# Z-Control-V2.net
KiCad netlist of a schematic drawn in EAGLE
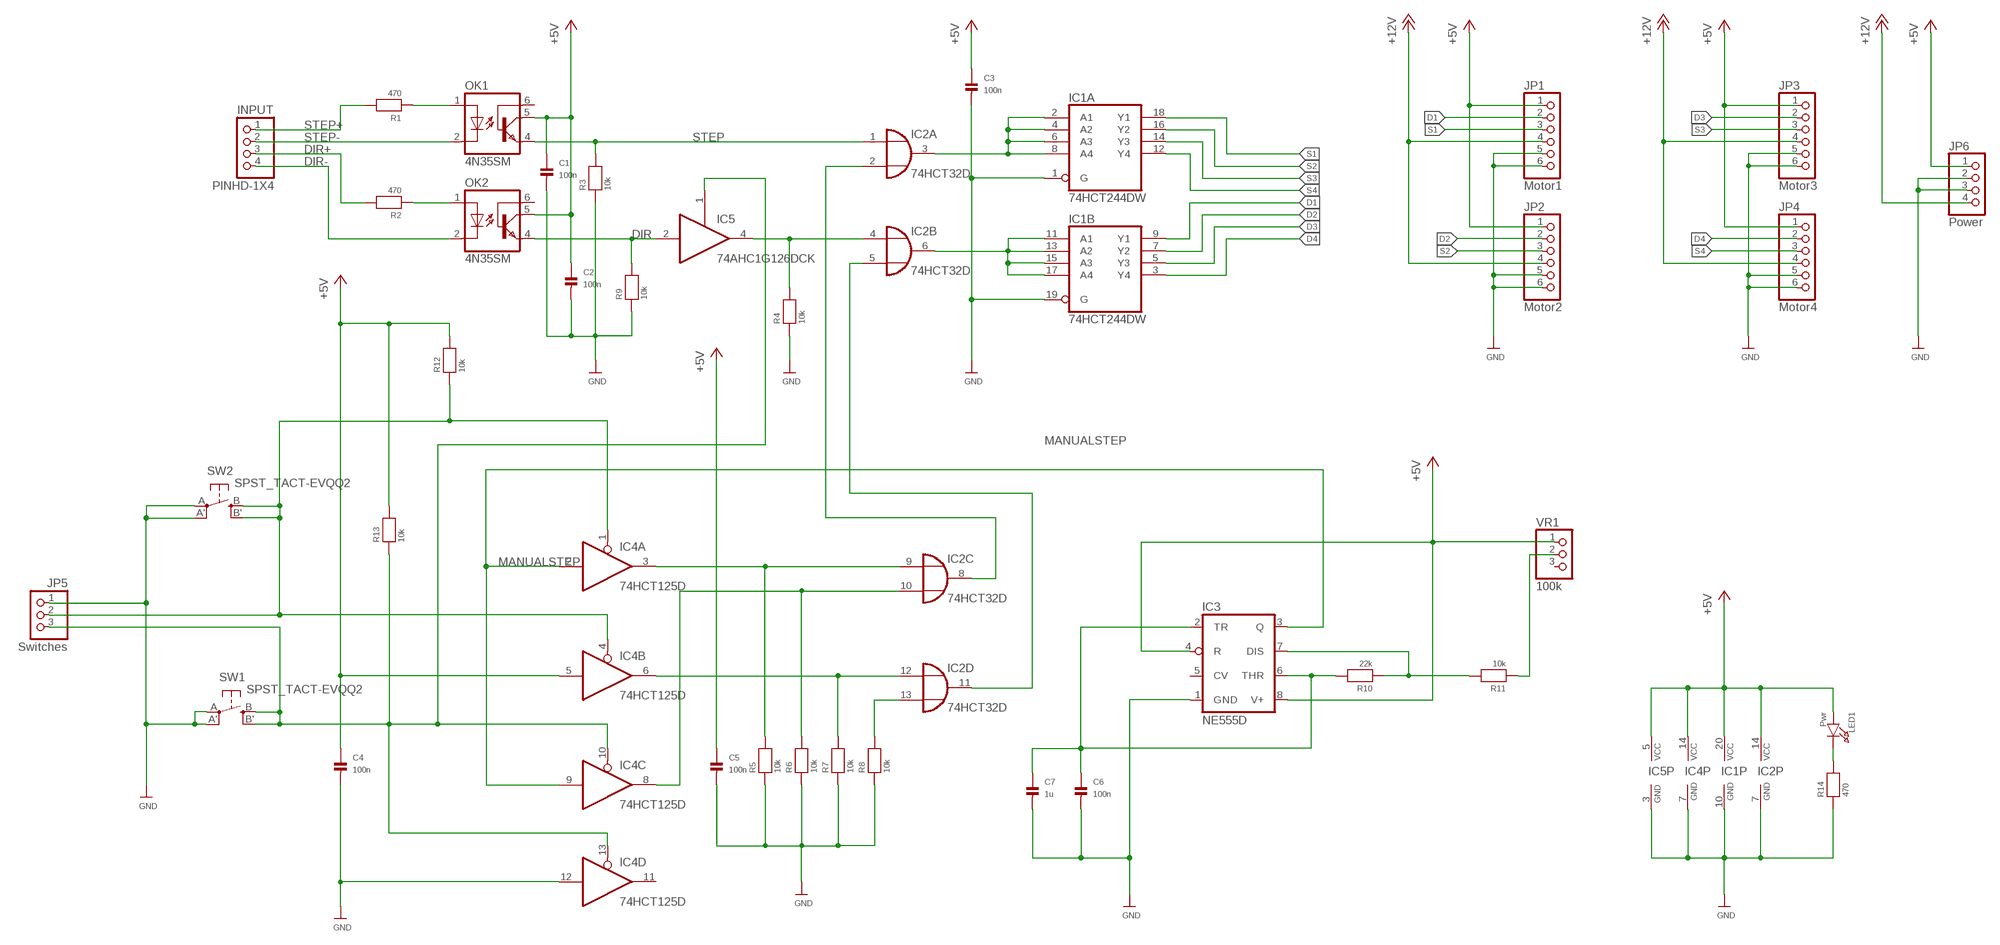
[diagram p0: schematic, sheet 1]

(export (version "E")
  (design (tool "Eeschema 10.0.6"))
  (components
    (comp (ref "C1")
      (value "100n")
      (footprint "eagle-import:_0805")
      (libsource (lib "eagle-import") (part "CAP_CERAMIC_0805"))
    )
    (comp (ref "C2")
      (value "100n")
      (footprint "eagle-import:_0805")
      (libsource (lib "eagle-import") (part "CAP_CERAMIC_0805"))
    )
    (comp (ref "C3")
      (value "100n")
      (footprint "eagle-import:_0805")
      (libsource (lib "eagle-import") (part "CAP_CERAMIC_0805"))
    )
    (comp (ref "C4")
      (value "100n")
      (footprint "eagle-import:_0805")
      (libsource (lib "eagle-import") (part "CAP_CERAMIC_0805"))
    )
    (comp (ref "C5")
      (value "100n")
      (footprint "eagle-import:_0805")
      (libsource (lib "eagle-import") (part "CAP_CERAMIC_0805"))
    )
    (comp (ref "C6")
      (value "100n")
      (footprint "eagle-import:_0805")
      (libsource (lib "eagle-import") (part "CAP_CERAMIC_0805"))
    )
    (comp (ref "C7")
      (value "1u")
      (footprint "eagle-import:_0805")
      (libsource (lib "eagle-import") (part "CAP_CERAMIC_0805"))
    )
    (comp (ref "IC1")
      (value "74HCT244DW")
      (footprint "eagle-import:SO20W")
      (libsource (lib "eagle-import") (part "74244DWHCT"))
    )
    (comp (ref "IC2")
      (value "74HCT32D")
      (footprint "eagle-import:SO14")
      (libsource (lib "eagle-import") (part "7432DHCT"))
    )
    (comp (ref "IC3")
      (value "NE555D")
      (footprint "eagle-import:SO08")
      (libsource (lib "eagle-import") (part "555DNE"))
    )
    (comp (ref "IC4")
      (value "74HCT125D")
      (footprint "eagle-import:SO14")
      (libsource (lib "eagle-import") (part "74125DHCT"))
    )
    (comp (ref "IC5")
      (value "74AHC1G126DCK")
      (footprint "eagle-import:SC70-5")
      (libsource (lib "eagle-import") (part "741G126DCKAHC"))
    )
    (comp (ref "INPUT")
      (value "PINHD-1X4")
      (footprint "eagle-import:1X04-BIG")
      (libsource (lib "eagle-import") (part "PINHD-1X4"))
    )
    (comp (ref "JP1")
      (value "Motor1")
      (footprint "eagle-import:1X06")
      (libsource (lib "eagle-import") (part "PINHD-1X6"))
    )
    (comp (ref "JP2")
      (value "Motor2")
      (footprint "eagle-import:1X06")
      (libsource (lib "eagle-import") (part "PINHD-1X6"))
    )
    (comp (ref "JP3")
      (value "Motor3")
      (footprint "eagle-import:1X06")
      (libsource (lib "eagle-import") (part "PINHD-1X6"))
    )
    (comp (ref "JP4")
      (value "Motor4")
      (footprint "eagle-import:1X06")
      (libsource (lib "eagle-import") (part "PINHD-1X6"))
    )
    (comp (ref "JP5")
      (value "Switches")
      (footprint "eagle-import:1X03")
      (libsource (lib "eagle-import") (part "PINHD-1X3"))
    )
    (comp (ref "JP6")
      (value "Power")
      (footprint "eagle-import:1X04-BIG")
      (libsource (lib "eagle-import") (part "PINHD-1X4"))
    )
    (comp (ref "LED1")
      (value "Pwr")
      (footprint "eagle-import:CHIPLED_0805")
      (libsource (lib "eagle-import") (part "LED0805"))
    )
    (comp (ref "OK1")
      (value "4N35SM")
      (footprint "eagle-import:DIL6-SMD")
      (fields (field (name "MF") "FAIRCHILD SEMICONDUCTOR") (field (name "MPN") "4N35S-M"))
      (libsource (lib "eagle-import") (part "4N?MS35"))
    )
    (comp (ref "OK2")
      (value "4N35SM")
      (footprint "eagle-import:DIL6-SMD")
      (fields (field (name "MF") "FAIRCHILD SEMICONDUCTOR") (field (name "MPN") "4N35S-M"))
      (libsource (lib "eagle-import") (part "4N?MS35"))
    )
    (comp (ref "R1")
      (value "470")
      (footprint "eagle-import:_0805")
      (libsource (lib "eagle-import") (part "RESISTOR_0805"))
    )
    (comp (ref "R2")
      (value "470")
      (footprint "eagle-import:_0805")
      (libsource (lib "eagle-import") (part "RESISTOR_0805"))
    )
    (comp (ref "R3")
      (value "10k")
      (footprint "eagle-import:_0805")
      (libsource (lib "eagle-import") (part "RESISTOR_0805"))
    )
    (comp (ref "R4")
      (value "10k")
      (footprint "eagle-import:_0805")
      (libsource (lib "eagle-import") (part "RESISTOR_0805"))
    )
    (comp (ref "R5")
      (value "10k")
      (footprint "eagle-import:_0805")
      (libsource (lib "eagle-import") (part "RESISTOR_0805"))
    )
    (comp (ref "R6")
      (value "10k")
      (footprint "eagle-import:_0805")
      (libsource (lib "eagle-import") (part "RESISTOR_0805"))
    )
    (comp (ref "R7")
      (value "10k")
      (footprint "eagle-import:_0805")
      (libsource (lib "eagle-import") (part "RESISTOR_0805"))
    )
    (comp (ref "R8")
      (value "10k")
      (footprint "eagle-import:_0805")
      (libsource (lib "eagle-import") (part "RESISTOR_0805"))
    )
    (comp (ref "R9")
      (value "10k")
      (footprint "eagle-import:_0805")
      (libsource (lib "eagle-import") (part "RESISTOR_0805"))
    )
    (comp (ref "R10")
      (value "22k")
      (footprint "eagle-import:_0805")
      (libsource (lib "eagle-import") (part "RESISTOR_0805"))
    )
    (comp (ref "R11")
      (value "10k")
      (footprint "eagle-import:_0805")
      (libsource (lib "eagle-import") (part "RESISTOR_0805"))
    )
    (comp (ref "R12")
      (value "10k")
      (footprint "eagle-import:_0805")
      (libsource (lib "eagle-import") (part "RESISTOR_0805"))
    )
    (comp (ref "R13")
      (value "10k")
      (footprint "eagle-import:_0805")
      (libsource (lib "eagle-import") (part "RESISTOR_0805"))
    )
    (comp (ref "R14")
      (value "470")
      (footprint "eagle-import:_0805")
      (libsource (lib "eagle-import") (part "RESISTOR_0805"))
    )
    (comp (ref "SW1")
      (value "SPST_TACT-EVQQ2")
      (footprint "eagle-import:EVQ-Q2")
      (libsource (lib "eagle-import") (part "SPST_TACT-EVQQ2"))
    )
    (comp (ref "SW2")
      (value "SPST_TACT-EVQQ2")
      (footprint "eagle-import:EVQ-Q2")
      (libsource (lib "eagle-import") (part "SPST_TACT-EVQQ2"))
    )
    (comp (ref "VR1")
      (value "100k")
      (footprint "eagle-import:1X03_OVAL")
      (libsource (lib "eagle-import") (part "HEADER-1X3"))
    )
  )
  (nets
    (net (code "1") (name "+5V") (class "Default")
      (node (ref "C1") (pin "1") (pinfunction "P$1_1") (pintype "passive"))
      (node (ref "C2") (pin "1") (pinfunction "P$1_1") (pintype "passive"))
      (node (ref "C3") (pin "1") (pinfunction "P$1_1") (pintype "passive"))
      (node (ref "C4") (pin "1") (pinfunction "P$1_1") (pintype "passive"))
      (node (ref "C5") (pin "1") (pinfunction "P$1_1") (pintype "passive"))
      (node (ref "IC1") (pin "20") (pinfunction "VCC_20") (pintype "power_in"))
      (node (ref "IC2") (pin "14") (pinfunction "VCC_14") (pintype "power_in"))
      (node (ref "IC3") (pin "4") (pinfunction "R_4") (pintype "input"))
      (node (ref "IC3") (pin "8") (pinfunction "V+_8") (pintype "power_in"))
      (node (ref "IC4") (pin "14") (pinfunction "VCC_14") (pintype "power_in"))
      (node (ref "IC4") (pin "5") (pinfunction "I_5") (pintype "input"))
      (node (ref "IC5") (pin "5") (pinfunction "VCC_5") (pintype "power_in"))
      (node (ref "JP1") (pin "1") (pinfunction "1_1") (pintype "passive"))
      (node (ref "JP2") (pin "1") (pinfunction "1_1") (pintype "passive"))
      (node (ref "JP3") (pin "1") (pinfunction "1_1") (pintype "passive"))
      (node (ref "JP4") (pin "1") (pinfunction "1_1") (pintype "passive"))
      (node (ref "JP6") (pin "1") (pinfunction "1_1") (pintype "passive"))
      (node (ref "LED1") (pin "A") (pinfunction "A_A") (pintype "passive"))
      (node (ref "OK1") (pin "5") (pinfunction "COL_5") (pintype "passive"))
      (node (ref "OK2") (pin "5") (pinfunction "COL_5") (pintype "passive"))
      (node (ref "R12") (pin "2") (pinfunction "2_2") (pintype "passive"))
      (node (ref "R13") (pin "2") (pinfunction "2_2") (pintype "passive"))
      (node (ref "VR1") (pin "1") (pinfunction "1_1") (pintype "passive"))
    )
    (net (code "2") (name "+12V") (class "Default")
      (node (ref "JP1") (pin "4") (pinfunction "4_4") (pintype "passive"))
      (node (ref "JP2") (pin "4") (pinfunction "4_4") (pintype "passive"))
      (node (ref "JP3") (pin "4") (pinfunction "4_4") (pintype "passive"))
      (node (ref "JP4") (pin "4") (pinfunction "4_4") (pintype "passive"))
      (node (ref "JP6") (pin "4") (pinfunction "4_4") (pintype "passive"))
    )
    (net (code "3") (name "/DIR") (class "Default")
      (node (ref "IC5") (pin "2") (pinfunction "I_2") (pintype "input"))
      (node (ref "OK2") (pin "4") (pinfunction "EMI_4") (pintype "passive"))
      (node (ref "R9") (pin "2") (pinfunction "2_2") (pintype "passive"))
    )
    (net (code "4") (name "/DIR+") (class "Default")
      (node (ref "INPUT") (pin "3") (pinfunction "3_3") (pintype "passive"))
      (node (ref "R2") (pin "2") (pinfunction "2_2") (pintype "passive"))
    )
    (net (code "5") (name "/DIR-") (class "Default")
      (node (ref "INPUT") (pin "4") (pinfunction "4_4") (pintype "passive"))
      (node (ref "OK2") (pin "2") (pinfunction "C_2") (pintype "passive"))
    )
    (net (code "6") (name "/MANUALSTEP") (class "Default")
      (node (ref "IC3") (pin "3") (pinfunction "Q_3") (pintype "output"))
      (node (ref "IC4") (pin "2") (pinfunction "I_2") (pintype "input"))
      (node (ref "IC4") (pin "9") (pinfunction "I_9") (pintype "input"))
    )
    (net (code "7") (name "/STEP") (class "Default")
      (node (ref "IC2") (pin "1") (pinfunction "I0_1") (pintype "input"))
      (node (ref "OK1") (pin "4") (pinfunction "EMI_4") (pintype "passive"))
      (node (ref "R3") (pin "2") (pinfunction "2_2") (pintype "passive"))
    )
    (net (code "8") (name "/STEP+") (class "Default")
      (node (ref "INPUT") (pin "1") (pinfunction "1_1") (pintype "passive"))
      (node (ref "R1") (pin "2") (pinfunction "2_2") (pintype "passive"))
    )
    (net (code "9") (name "/STEP-") (class "Default")
      (node (ref "INPUT") (pin "2") (pinfunction "2_2") (pintype "passive"))
      (node (ref "OK1") (pin "2") (pinfunction "C_2") (pintype "passive"))
    )
    (net (code "10") (name "D1") (class "Default")
      (node (ref "IC1") (pin "9") (pinfunction "Y1_9") (pintype "tri_state"))
      (node (ref "JP1") (pin "2") (pinfunction "2_2") (pintype "passive"))
    )
    (net (code "11") (name "D2") (class "Default")
      (node (ref "IC1") (pin "7") (pinfunction "Y2_7") (pintype "tri_state"))
      (node (ref "JP2") (pin "2") (pinfunction "2_2") (pintype "passive"))
    )
    (net (code "12") (name "D3") (class "Default")
      (node (ref "IC1") (pin "5") (pinfunction "Y3_5") (pintype "tri_state"))
      (node (ref "JP3") (pin "2") (pinfunction "2_2") (pintype "passive"))
    )
    (net (code "13") (name "D4") (class "Default")
      (node (ref "IC1") (pin "3") (pinfunction "Y4_3") (pintype "tri_state"))
      (node (ref "JP4") (pin "2") (pinfunction "2_2") (pintype "passive"))
    )
    (net (code "14") (name "GND") (class "Default")
      (node (ref "C1") (pin "2") (pinfunction "P$2_2") (pintype "passive"))
      (node (ref "C2") (pin "2") (pinfunction "P$2_2") (pintype "passive"))
      (node (ref "C3") (pin "2") (pinfunction "P$2_2") (pintype "passive"))
      (node (ref "C4") (pin "2") (pinfunction "P$2_2") (pintype "passive"))
      (node (ref "C5") (pin "2") (pinfunction "P$2_2") (pintype "passive"))
      (node (ref "C6") (pin "2") (pinfunction "P$2_2") (pintype "passive"))
      (node (ref "C7") (pin "2") (pinfunction "P$2_2") (pintype "passive"))
      (node (ref "IC1") (pin "1") (pinfunction "G_1") (pintype "input"))
      (node (ref "IC1") (pin "10") (pinfunction "GND_10") (pintype "power_in"))
      (node (ref "IC1") (pin "19") (pinfunction "G_19") (pintype "input"))
      (node (ref "IC2") (pin "7") (pinfunction "GND_7") (pintype "power_in"))
      (node (ref "IC3") (pin "1") (pinfunction "GND_1") (pintype "power_in"))
      (node (ref "IC4") (pin "12") (pinfunction "I_12") (pintype "input"))
      (node (ref "IC4") (pin "7") (pinfunction "GND_7") (pintype "power_in"))
      (node (ref "IC5") (pin "3") (pinfunction "GND_3") (pintype "power_in"))
      (node (ref "JP1") (pin "5") (pinfunction "5_5") (pintype "passive"))
      (node (ref "JP1") (pin "6") (pinfunction "6_6") (pintype "passive"))
      (node (ref "JP2") (pin "5") (pinfunction "5_5") (pintype "passive"))
      (node (ref "JP2") (pin "6") (pinfunction "6_6") (pintype "passive"))
      (node (ref "JP3") (pin "5") (pinfunction "5_5") (pintype "passive"))
      (node (ref "JP3") (pin "6") (pinfunction "6_6") (pintype "passive"))
      (node (ref "JP4") (pin "5") (pinfunction "5_5") (pintype "passive"))
      (node (ref "JP4") (pin "6") (pinfunction "6_6") (pintype "passive"))
      (node (ref "JP5") (pin "1") (pinfunction "1_1") (pintype "passive"))
      (node (ref "JP6") (pin "2") (pinfunction "2_2") (pintype "passive"))
      (node (ref "JP6") (pin "3") (pinfunction "3_3") (pintype "passive"))
      (node (ref "R14") (pin "1") (pinfunction "1_1") (pintype "passive"))
      (node (ref "R3") (pin "1") (pinfunction "1_1") (pintype "passive"))
      (node (ref "R4") (pin "1") (pinfunction "1_1") (pintype "passive"))
      (node (ref "R5") (pin "1") (pinfunction "1_1") (pintype "passive"))
      (node (ref "R6") (pin "1") (pinfunction "1_1") (pintype "passive"))
      (node (ref "R7") (pin "1") (pinfunction "1_1") (pintype "passive"))
      (node (ref "R8") (pin "1") (pinfunction "1_1") (pintype "passive"))
      (node (ref "R9") (pin "1") (pinfunction "1_1") (pintype "passive"))
      (node (ref "SW1") (pin "A") (pinfunction "P_A") (pintype "passive"))
      (node (ref "SW1") (pin "A'") (pinfunction "P1_A'") (pintype "passive"))
      (node (ref "SW2") (pin "A") (pinfunction "P_A") (pintype "passive"))
      (node (ref "SW2") (pin "A'") (pinfunction "P1_A'") (pintype "passive"))
    )
    (net (code "15") (name "Net-(C6-P$1)") (class "Default")
      (node (ref "C6") (pin "1") (pinfunction "P$1_1") (pintype "passive"))
      (node (ref "C7") (pin "1") (pinfunction "P$1_1") (pintype "passive"))
      (node (ref "IC3") (pin "2") (pinfunction "TR_2") (pintype "input"))
      (node (ref "IC3") (pin "6") (pinfunction "THR_6") (pintype "input"))
      (node (ref "R10") (pin "2") (pinfunction "2_2") (pintype "passive"))
    )
    (net (code "16") (name "Net-(IC1A-A1)") (class "Default")
      (node (ref "IC1") (pin "2") (pinfunction "A1_2") (pintype "input"))
      (node (ref "IC1") (pin "4") (pinfunction "A2_4") (pintype "input"))
      (node (ref "IC1") (pin "6") (pinfunction "A3_6") (pintype "input"))
      (node (ref "IC1") (pin "8") (pinfunction "A4_8") (pintype "input"))
      (node (ref "IC2") (pin "3") (pinfunction "O_3") (pintype "output"))
    )
    (net (code "17") (name "Net-(IC1B-A1)") (class "Default")
      (node (ref "IC1") (pin "11") (pinfunction "A1_11") (pintype "input"))
      (node (ref "IC1") (pin "13") (pinfunction "A2_13") (pintype "input"))
      (node (ref "IC1") (pin "15") (pinfunction "A3_15") (pintype "input"))
      (node (ref "IC1") (pin "17") (pinfunction "A4_17") (pintype "input"))
      (node (ref "IC2") (pin "6") (pinfunction "O_6") (pintype "output"))
    )
    (net (code "18") (name "Net-(IC2A-I1)") (class "Default")
      (node (ref "IC2") (pin "2") (pinfunction "I1_2") (pintype "input"))
      (node (ref "IC2") (pin "8") (pinfunction "O_8") (pintype "output"))
    )
    (net (code "19") (name "Net-(IC2B-I0)") (class "Default")
      (node (ref "IC2") (pin "4") (pinfunction "I0_4") (pintype "input"))
      (node (ref "IC5") (pin "4") (pinfunction "O_4") (pintype "output"))
      (node (ref "R4") (pin "2") (pinfunction "2_2") (pintype "passive"))
    )
    (net (code "20") (name "Net-(IC2B-I1)") (class "Default")
      (node (ref "IC2") (pin "11") (pinfunction "O_11") (pintype "output"))
      (node (ref "IC2") (pin "5") (pinfunction "I1_5") (pintype "input"))
    )
    (net (code "21") (name "Net-(IC2C-I0)") (class "Default")
      (node (ref "IC2") (pin "9") (pinfunction "I0_9") (pintype "input"))
      (node (ref "IC4") (pin "3") (pinfunction "O_3") (pintype "tri_state"))
      (node (ref "R5") (pin "2") (pinfunction "2_2") (pintype "passive"))
    )
    (net (code "22") (name "Net-(IC2C-I1)") (class "Default")
      (node (ref "IC2") (pin "10") (pinfunction "I1_10") (pintype "input"))
      (node (ref "IC4") (pin "8") (pinfunction "O_8") (pintype "tri_state"))
      (node (ref "R6") (pin "2") (pinfunction "2_2") (pintype "passive"))
    )
    (net (code "23") (name "Net-(IC2D-I0)") (class "Default")
      (node (ref "IC2") (pin "12") (pinfunction "I0_12") (pintype "input"))
      (node (ref "IC4") (pin "6") (pinfunction "O_6") (pintype "tri_state"))
      (node (ref "R7") (pin "2") (pinfunction "2_2") (pintype "passive"))
    )
    (net (code "24") (name "Net-(IC2D-I1)") (class "Default")
      (node (ref "IC2") (pin "13") (pinfunction "I1_13") (pintype "input"))
      (node (ref "R8") (pin "2") (pinfunction "2_2") (pintype "passive"))
    )
    (net (code "25") (name "Net-(IC3-DIS)") (class "Default")
      (node (ref "IC3") (pin "7") (pinfunction "DIS_7") (pintype "input"))
      (node (ref "R10") (pin "1") (pinfunction "1_1") (pintype "passive"))
      (node (ref "R11") (pin "2") (pinfunction "2_2") (pintype "passive"))
    )
    (net (code "26") (name "Net-(IC4A-OE)") (class "Default")
      (node (ref "IC4") (pin "1") (pinfunction "OE_1") (pintype "input"))
      (node (ref "IC4") (pin "4") (pinfunction "OE_4") (pintype "input"))
      (node (ref "JP5") (pin "2") (pinfunction "2_2") (pintype "passive"))
      (node (ref "R12") (pin "1") (pinfunction "1_1") (pintype "passive"))
      (node (ref "SW2") (pin "B") (pinfunction "S_B") (pintype "passive"))
      (node (ref "SW2") (pin "B'") (pinfunction "S1_B'") (pintype "passive"))
    )
    (net (code "27") (name "Net-(IC4C-OE)") (class "Default")
      (node (ref "IC4") (pin "10") (pinfunction "OE_10") (pintype "input"))
      (node (ref "IC4") (pin "13") (pinfunction "OE_13") (pintype "input"))
      (node (ref "IC5") (pin "1") (pinfunction "OE_1") (pintype "input"))
      (node (ref "JP5") (pin "3") (pinfunction "3_3") (pintype "passive"))
      (node (ref "R13") (pin "1") (pinfunction "1_1") (pintype "passive"))
      (node (ref "SW1") (pin "B") (pinfunction "S_B") (pintype "passive"))
      (node (ref "SW1") (pin "B'") (pinfunction "S1_B'") (pintype "passive"))
    )
    (net (code "28") (name "Net-(LED1-PadC)") (class "Default")
      (node (ref "LED1") (pin "C") (pinfunction "C_C") (pintype "passive"))
      (node (ref "R14") (pin "2") (pinfunction "2_2") (pintype "passive"))
    )
    (net (code "29") (name "Net-(OK1-A)") (class "Default")
      (node (ref "OK1") (pin "1") (pinfunction "A_1") (pintype "passive"))
      (node (ref "R1") (pin "1") (pinfunction "1_1") (pintype "passive"))
    )
    (net (code "30") (name "Net-(OK2-A)") (class "Default")
      (node (ref "OK2") (pin "1") (pinfunction "A_1") (pintype "passive"))
      (node (ref "R2") (pin "1") (pinfunction "1_1") (pintype "passive"))
    )
    (net (code "31") (name "Net-(R11-Pad1)") (class "Default")
      (node (ref "R11") (pin "1") (pinfunction "1_1") (pintype "passive"))
      (node (ref "VR1") (pin "2") (pinfunction "2_2") (pintype "passive"))
    )
    (net (code "32") (name "S1") (class "Default")
      (node (ref "IC1") (pin "18") (pinfunction "Y1_18") (pintype "tri_state"))
      (node (ref "JP1") (pin "3") (pinfunction "3_3") (pintype "passive"))
    )
    (net (code "33") (name "S2") (class "Default")
      (node (ref "IC1") (pin "16") (pinfunction "Y2_16") (pintype "tri_state"))
      (node (ref "JP2") (pin "3") (pinfunction "3_3") (pintype "passive"))
    )
    (net (code "34") (name "S3") (class "Default")
      (node (ref "IC1") (pin "14") (pinfunction "Y3_14") (pintype "tri_state"))
      (node (ref "JP3") (pin "3") (pinfunction "3_3") (pintype "passive"))
    )
    (net (code "35") (name "S4") (class "Default")
      (node (ref "IC1") (pin "12") (pinfunction "Y4_12") (pintype "tri_state"))
      (node (ref "JP4") (pin "3") (pinfunction "3_3") (pintype "passive"))
    )
    (net (code "36") (name "unconnected-(IC3-CV-Pad5)") (class "Default")
      (node (ref "IC3") (pin "5") (pinfunction "CV_5") (pintype "input"))
    )
    (net (code "37") (name "unconnected-(IC4D-O-Pad11)") (class "Default")
      (node (ref "IC4") (pin "11") (pinfunction "O_11") (pintype "tri_state"))
    )
    (net (code "38") (name "unconnected-(OK1-BAS-Pad6)") (class "Default")
      (node (ref "OK1") (pin "6") (pinfunction "BAS_6") (pintype "passive"))
    )
    (net (code "39") (name "unconnected-(OK2-BAS-Pad6)") (class "Default")
      (node (ref "OK2") (pin "6") (pinfunction "BAS_6") (pintype "passive"))
    )
    (net (code "40") (name "unconnected-(VR1-Pad3)") (class "Default")
      (node (ref "VR1") (pin "3") (pinfunction "3_3") (pintype "passive"))
    )
  )
)
